# MRBR_2020-10-03_09-19-58.net
KiCad netlist of a schematic drawn in EasyEDA
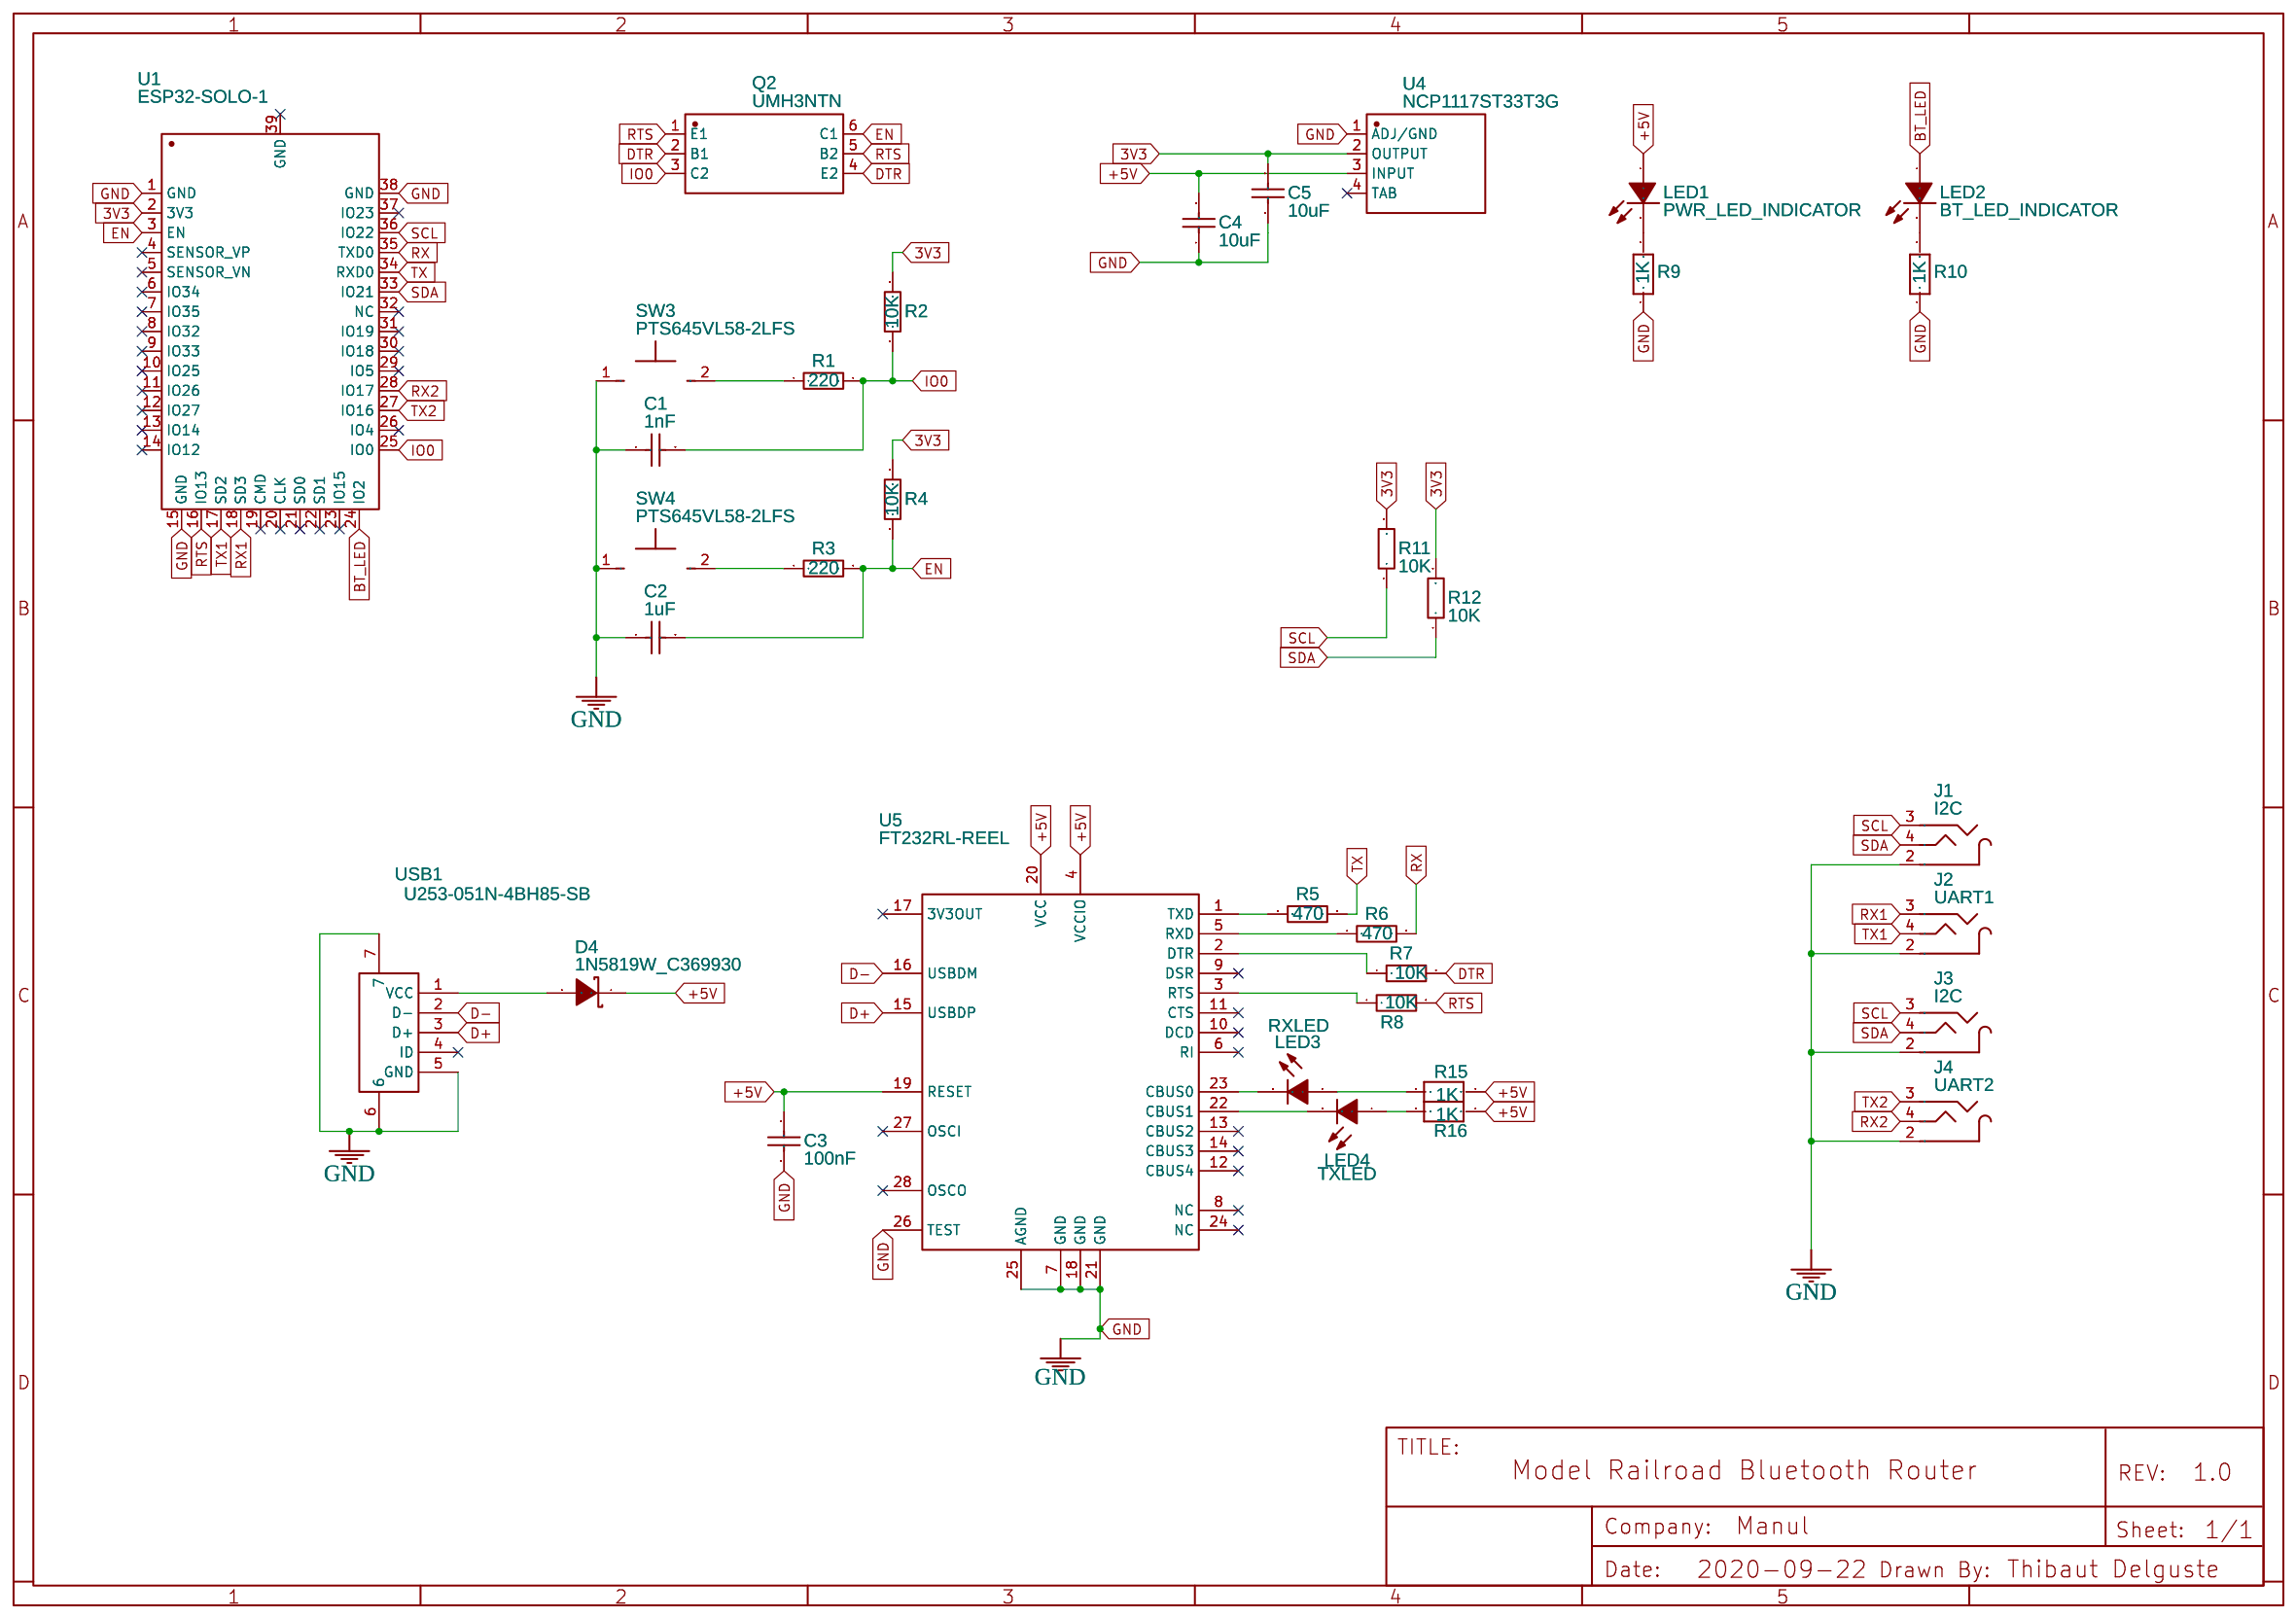
[diagram p0: schematic sheet]

(export (version "E")
  (design (tool "Eeschema 10.0.6"))
  (components
    (comp (ref "C1")
      (value "1nF")
      (fields
        (field (name "BOM_Manufacturer Part") "1206B102K500NT")
        (field (name "BOM_Supplier Part") "C1845")
      )
      (libsource (lib "") (part "1206B102K500NT"))
    )
    (comp (ref "C2")
      (value "1uF")
      (fields
        (field (name "BOM_Manufacturer Part") "1206B102K500NT")
        (field (name "BOM_Supplier Part") "C1845")
      )
      (libsource (lib "") (part "1206B102K500NT"))
    )
    (comp (ref "C3")
      (value "100nF")
      (fields
        (field (name "BOM_Manufacturer Part") "CL31B104KBCNNNC")
        (field (name "BOM_Supplier Part") "C24497")
      )
      (libsource (lib "") (part "CL31B104KBCNNNC"))
    )
    (comp (ref "C4")
      (value "10uF")
      (fields
        (field (name "BOM_Manufacturer Part") "CL31A106KAHNNNE")
        (field (name "BOM_Supplier Part") "C9807")
      )
      (libsource (lib "") (part "CL31A106KAHNNNE"))
    )
    (comp (ref "C5")
      (value "10uF")
      (fields
        (field (name "BOM_Manufacturer Part") "CL31A106KAHNNNE")
        (field (name "BOM_Supplier Part") "C9807")
      )
      (libsource (lib "") (part "CL31A106KAHNNNE"))
    )
    (comp (ref "D4")
      (value "1N5819W_C369930")
      (fields (field (name "BOM_Manufacturer Part") "1N5819W") (field (name "BOM_Supplier Part") "C369930"))
      (libsource (lib "") (part "1N5819W_C369930"))
    )
    (comp (ref "J1")
      (value "I2C")
      (fields (field (name "BOM_Manufacturer Part") "PJ313D") (field (name "BOM_Supplier Part") "C18167"))
      (libsource (lib "") (part "PJ313D"))
    )
    (comp (ref "J2")
      (value "UART1")
      (fields (field (name "BOM_Manufacturer Part") "PJ313D") (field (name "BOM_Supplier Part") "C18167"))
      (libsource (lib "") (part "PJ313D"))
    )
    (comp (ref "J3")
      (value "I2C")
      (fields (field (name "BOM_Manufacturer Part") "PJ313D") (field (name "BOM_Supplier Part") "C18167"))
      (libsource (lib "") (part "PJ313D"))
    )
    (comp (ref "J4")
      (value "UART2")
      (fields (field (name "BOM_Manufacturer Part") "PJ313D") (field (name "BOM_Supplier Part") "C18167"))
      (libsource (lib "") (part "PJ313D"))
    )
    (comp (ref "LED1")
      (value "PWR_LED_INDICATOR")
      (fields
        (field (name "BOM_Manufacturer Part") "FC-3215HRK-620D")
        (field (name "BOM_Supplier Part") "C84270")
      )
      (libsource (lib "") (part "FC-3215HRK-620D"))
    )
    (comp (ref "LED2")
      (value "BT_LED_INDICATOR")
      (fields
        (field (name "BOM_Manufacturer Part") "FC-3215HRK-620D")
        (field (name "BOM_Supplier Part") "C84270")
      )
      (libsource (lib "") (part "FC-3215HRK-620D"))
    )
    (comp (ref "LED3")
      (value "RXLED")
      (fields
        (field (name "BOM_Manufacturer Part") "15-21SYGC/S530-E2/TR8")
        (field (name "BOM_Supplier Part") "C73550")
      )
      (libsource (lib "") (part "15-21SYGC/S530-E2/TR8_1"))
    )
    (comp (ref "LED4")
      (value "TXLED")
      (fields
        (field (name "BOM_Manufacturer Part") "15-21SYGC/S530-E2/TR8")
        (field (name "BOM_Supplier Part") "C73550")
      )
      (libsource (lib "") (part "15-21SYGC/S530-E2/TR8"))
    )
    (comp (ref "Q2")
      (value "UMH3NTN")
      (fields (field (name "BOM_Supplier Part") "C123008"))
      (libsource (lib "") (part "UMH3NTN"))
    )
    (comp (ref "R1")
      (value "220")
      (fields
        (field (name "BOM_Manufacturer Part") "CR1206F42200G")
        (field (name "BOM_Supplier Part") "C102128")
      )
      (libsource (lib "") (part "CR1206F42200G"))
    )
    (comp (ref "R2")
      (value "10K")
      (fields
        (field (name "BOM_Manufacturer Part") "1206W4F1002T5E")
        (field (name "BOM_Supplier Part") "C17902")
      )
      (libsource (lib "") (part "1206W4F1002T5E"))
    )
    (comp (ref "R3")
      (value "220")
      (fields
        (field (name "BOM_Manufacturer Part") "CR1206F42200G")
        (field (name "BOM_Supplier Part") "C102128")
      )
      (libsource (lib "") (part "CR1206F42200G"))
    )
    (comp (ref "R4")
      (value "10K")
      (fields
        (field (name "BOM_Manufacturer Part") "1206W4F1002T5E")
        (field (name "BOM_Supplier Part") "C17902")
      )
      (libsource (lib "") (part "1206W4F1002T5E"))
    )
    (comp (ref "R5")
      (value "470")
      (fields
        (field (name "BOM_Manufacturer Part") "RCT06470RFLF")
        (field (name "BOM_Supplier Part") "C185720")
      )
      (libsource (lib "") (part "RCT06470RFLF"))
    )
    (comp (ref "R6")
      (value "470")
      (fields
        (field (name "BOM_Manufacturer Part") "RCT06470RFLF")
        (field (name "BOM_Supplier Part") "C185720")
      )
      (libsource (lib "") (part "RCT06470RFLF"))
    )
    (comp (ref "R7")
      (value "10K")
      (fields
        (field (name "BOM_Manufacturer Part") "1206W4J0102T5E")
        (field (name "BOM_Supplier Part") "C1469")
      )
      (libsource (lib "") (part "1206W4J0102T5E"))
    )
    (comp (ref "R8")
      (value "10K")
      (fields
        (field (name "BOM_Manufacturer Part") "1206W4J0102T5E")
        (field (name "BOM_Supplier Part") "C1469")
      )
      (libsource (lib "") (part "1206W4J0102T5E"))
    )
    (comp (ref "R9") (value "1K") (libsource (lib "") (part "Unknown_825_-675")))
    (comp (ref "R10") (value "1K") (libsource (lib "") (part "Unknown_965_-675")))
    (comp (ref "R11")
      (value "10K")
      (fields
        (field (name "BOM_Manufacturer Part") "1206W4J0102T5E")
        (field (name "BOM_Supplier Part") "C1469")
      )
      (libsource (lib "") (part "1206W4J0102T5E_1"))
    )
    (comp (ref "R12")
      (value "10K")
      (fields
        (field (name "BOM_Manufacturer Part") "1206W4J0102T5E")
        (field (name "BOM_Supplier Part") "C1469")
      )
      (libsource (lib "") (part "1206W4J0102T5E_1"))
    )
    (comp (ref "R15") (value "1K") (libsource (lib "") (part "Unknown_725_-260")))
    (comp (ref "R16") (value "1K") (libsource (lib "") (part "Unknown_725_-250")))
    (comp (ref "SW3")
      (value "PTS645VL58-2LFS")
      (fields (field (name "BOM_Supplier Part") "C221892"))
      (libsource (lib "") (part "Unknown_325_-630"))
    )
    (comp (ref "SW4")
      (value "PTS645VL58-2LFS")
      (fields (field (name "BOM_Supplier Part") "C221892"))
      (libsource (lib "") (part "Unknown_325_-535"))
    )
    (comp (ref "U1")
      (value "ESP32-SOLO-1")
      (fields (field (name "BOM_Supplier Part") "C473005"))
      (libsource (lib "") (part "ESP32-SOLO-1"))
    )
    (comp (ref "U4")
      (value "NCP1117ST33T3G")
      (fields (field (name "BOM_Supplier Part") "C26537"))
      (libsource (lib "") (part "NCP1117ST33T3G"))
    )
    (comp (ref "U5")
      (value "FT232RL-REEL")
      (fields (field (name "BOM_Supplier Part") "C8690"))
      (libsource (lib "") (part "Unknown_530_-270"))
    )
    (comp (ref "USB1")
      (value "U253-051N-4BH85-SB")
      (fields (field (name "BOM_Supplier Part") "C319177"))
      (libsource (lib "") (part "U253-051N-4BH85-SB"))
    )
  )
  (nets
    (net (code "1") (name "+5V") (class "Default")
      (node (ref "C3") (pin "2") (pinfunction "2_2") (pintype "input"))
      (node (ref "C4") (pin "2") (pinfunction "2_2") (pintype "input"))
      (node (ref "D4") (pin "1") (pinfunction "K_1") (pintype "unspecified"))
      (node (ref "LED1") (pin "1") (pinfunction "A_1") (pintype "unspecified"))
      (node (ref "R15") (pin "2") (pinfunction "2_2") (pintype "bidirectional"))
      (node (ref "R16") (pin "2") (pinfunction "2_2") (pintype "bidirectional"))
      (node (ref "U4") (pin "3") (pinfunction "INPUT_3") (pintype "unspecified"))
      (node (ref "U5") (pin "19") (pinfunction "RESET_19") (pintype "unspecified"))
      (node (ref "U5") (pin "20") (pinfunction "VCC_20") (pintype "passive"))
      (node (ref "U5") (pin "4") (pinfunction "VCCIO_4") (pintype "passive"))
    )
    (net (code "2") (name "3V3") (class "Default")
      (node (ref "C5") (pin "2") (pinfunction "2_2") (pintype "input"))
      (node (ref "R11") (pin "2") (pinfunction "2_2") (pintype "input"))
      (node (ref "R12") (pin "2") (pinfunction "2_2") (pintype "input"))
      (node (ref "R2") (pin "2") (pinfunction "2_2") (pintype "input"))
      (node (ref "R4") (pin "2") (pinfunction "2_2") (pintype "input"))
      (node (ref "U1") (pin "2") (pinfunction "3V3_2") (pintype "unspecified"))
      (node (ref "U4") (pin "2") (pinfunction "OUTPUT_2") (pintype "unspecified"))
    )
    (net (code "3") (name "BT_LED") (class "Default")
      (node (ref "LED2") (pin "1") (pinfunction "A_1") (pintype "unspecified"))
      (node (ref "U1") (pin "24") (pinfunction "IO2_24") (pintype "unspecified"))
    )
    (net (code "4") (name "D+") (class "Default")
      (node (ref "U5") (pin "15") (pinfunction "USBDP_15") (pintype "bidirectional"))
      (node (ref "USB1") (pin "3") (pinfunction "D+_3") (pintype "unspecified"))
    )
    (net (code "5") (name "D-") (class "Default")
      (node (ref "U5") (pin "16") (pinfunction "USBDM_16") (pintype "bidirectional"))
      (node (ref "USB1") (pin "2") (pinfunction "D-_2") (pintype "unspecified"))
    )
    (net (code "6") (name "DTR") (class "Default")
      (node (ref "Q2") (pin "2") (pinfunction "B1_2") (pintype "unspecified"))
      (node (ref "Q2") (pin "4") (pinfunction "E2_4") (pintype "unspecified"))
      (node (ref "R7") (pin "2") (pinfunction "2_2") (pintype "input"))
    )
    (net (code "7") (name "EN") (class "Default")
      (node (ref "C2") (pin "2") (pinfunction "2_2") (pintype "input"))
      (node (ref "Q2") (pin "6") (pinfunction "C1_6") (pintype "unspecified"))
      (node (ref "R3") (pin "2") (pinfunction "2_2") (pintype "input"))
      (node (ref "R4") (pin "1") (pinfunction "1_1") (pintype "input"))
      (node (ref "U1") (pin "3") (pinfunction "EN_3") (pintype "unspecified"))
    )
    (net (code "8") (name "GND") (class "Default")
      (node (ref "C1") (pin "1") (pinfunction "1_1") (pintype "input"))
      (node (ref "C2") (pin "1") (pinfunction "1_1") (pintype "input"))
      (node (ref "C3") (pin "1") (pinfunction "1_1") (pintype "input"))
      (node (ref "C4") (pin "1") (pinfunction "1_1") (pintype "input"))
      (node (ref "C5") (pin "1") (pinfunction "1_1") (pintype "input"))
      (node (ref "J1") (pin "2") (pinfunction "2_2") (pintype "input"))
      (node (ref "J2") (pin "2") (pinfunction "2_2") (pintype "input"))
      (node (ref "J3") (pin "2") (pinfunction "2_2") (pintype "input"))
      (node (ref "J4") (pin "2") (pinfunction "2_2") (pintype "input"))
      (node (ref "R10") (pin "1") (pinfunction "1_1") (pintype "bidirectional"))
      (node (ref "R9") (pin "1") (pinfunction "1_1") (pintype "bidirectional"))
      (node (ref "SW3") (pin "1") (pinfunction "1_1") (pintype "input"))
      (node (ref "SW4") (pin "1") (pinfunction "1_1") (pintype "input"))
      (node (ref "U1") (pin "1") (pinfunction "GND_1") (pintype "unspecified"))
      (node (ref "U1") (pin "15") (pinfunction "GND_15") (pintype "unspecified"))
      (node (ref "U1") (pin "38") (pinfunction "GND_38") (pintype "unspecified"))
      (node (ref "U4") (pin "1") (pinfunction "ADJ/GND_1") (pintype "unspecified"))
      (node (ref "U5") (pin "18") (pinfunction "GND_18") (pintype "passive"))
      (node (ref "U5") (pin "21") (pinfunction "GND_21") (pintype "passive"))
      (node (ref "U5") (pin "25") (pinfunction "AGND_25") (pintype "passive"))
      (node (ref "U5") (pin "26") (pinfunction "TEST_26") (pintype "unspecified"))
      (node (ref "U5") (pin "7") (pinfunction "GND_7") (pintype "passive"))
      (node (ref "USB1") (pin "5") (pinfunction "GND_5") (pintype "unspecified"))
      (node (ref "USB1") (pin "6") (pinfunction "6_6") (pintype "unspecified"))
      (node (ref "USB1") (pin "7") (pinfunction "7_7") (pintype "unspecified"))
    )
    (net (code "9") (name "IO0") (class "Default")
      (node (ref "C1") (pin "2") (pinfunction "2_2") (pintype "input"))
      (node (ref "Q2") (pin "3") (pinfunction "C2_3") (pintype "unspecified"))
      (node (ref "R1") (pin "2") (pinfunction "2_2") (pintype "input"))
      (node (ref "R2") (pin "1") (pinfunction "1_1") (pintype "input"))
      (node (ref "U1") (pin "25") (pinfunction "IO0_25") (pintype "unspecified"))
    )
    (net (code "10") (name "Net-(D4-A)") (class "Default")
      (node (ref "D4") (pin "2") (pinfunction "A_2") (pintype "unspecified"))
      (node (ref "USB1") (pin "1") (pinfunction "VCC_1") (pintype "unspecified"))
    )
    (net (code "11") (name "Net-(LED1-K)") (class "Default")
      (node (ref "LED1") (pin "2") (pinfunction "K_2") (pintype "unspecified"))
      (node (ref "R9") (pin "2") (pinfunction "2_2") (pintype "bidirectional"))
    )
    (net (code "12") (name "Net-(LED2-K)") (class "Default")
      (node (ref "LED2") (pin "2") (pinfunction "K_2") (pintype "unspecified"))
      (node (ref "R10") (pin "2") (pinfunction "2_2") (pintype "bidirectional"))
    )
    (net (code "13") (name "Net-(LED3-A)") (class "Default")
      (node (ref "LED3") (pin "1") (pinfunction "A_1") (pintype "input"))
      (node (ref "R15") (pin "1") (pinfunction "1_1") (pintype "bidirectional"))
    )
    (net (code "14") (name "Net-(LED3-C)") (class "Default")
      (node (ref "LED3") (pin "2") (pinfunction "C_2") (pintype "input"))
      (node (ref "U5") (pin "23") (pinfunction "CBUS0_23") (pintype "bidirectional"))
    )
    (net (code "15") (name "Net-(LED4-A)") (class "Default")
      (node (ref "LED4") (pin "1") (pinfunction "A_1") (pintype "input"))
      (node (ref "R16") (pin "1") (pinfunction "1_1") (pintype "bidirectional"))
    )
    (net (code "16") (name "Net-(LED4-C)") (class "Default")
      (node (ref "LED4") (pin "2") (pinfunction "C_2") (pintype "input"))
      (node (ref "U5") (pin "22") (pinfunction "CBUS1_22") (pintype "bidirectional"))
    )
    (net (code "17") (name "Net-(R1-Pad1)") (class "Default")
      (node (ref "R1") (pin "1") (pinfunction "1_1") (pintype "input"))
      (node (ref "SW3") (pin "2") (pinfunction "2_2") (pintype "input"))
    )
    (net (code "18") (name "Net-(R3-Pad1)") (class "Default")
      (node (ref "R3") (pin "1") (pinfunction "1_1") (pintype "input"))
      (node (ref "SW4") (pin "2") (pinfunction "2_2") (pintype "input"))
    )
    (net (code "19") (name "Net-(U5-DTR)") (class "Default")
      (node (ref "R7") (pin "1") (pinfunction "1_1") (pintype "input"))
      (node (ref "U5") (pin "2") (pinfunction "DTR_2") (pintype "output"))
    )
    (net (code "20") (name "Net-(U5-RTS)") (class "Default")
      (node (ref "R8") (pin "1") (pinfunction "1_1") (pintype "input"))
      (node (ref "U5") (pin "3") (pinfunction "RTS_3") (pintype "output"))
    )
    (net (code "21") (name "Net-(U5-RXD)") (class "Default")
      (node (ref "R6") (pin "1") (pinfunction "1_1") (pintype "unspecified"))
      (node (ref "U5") (pin "5") (pinfunction "RXD_5") (pintype "unspecified"))
    )
    (net (code "22") (name "Net-(U5-TXD)") (class "Default")
      (node (ref "R5") (pin "1") (pinfunction "1_1") (pintype "unspecified"))
      (node (ref "U5") (pin "1") (pinfunction "TXD_1") (pintype "output"))
    )
    (net (code "23") (name "RTS") (class "Default")
      (node (ref "Q2") (pin "1") (pinfunction "E1_1") (pintype "unspecified"))
      (node (ref "Q2") (pin "5") (pinfunction "B2_5") (pintype "unspecified"))
      (node (ref "R8") (pin "2") (pinfunction "2_2") (pintype "input"))
      (node (ref "U1") (pin "16") (pinfunction "IO13_16") (pintype "unspecified"))
    )
    (net (code "24") (name "RX") (class "Default")
      (node (ref "R6") (pin "2") (pinfunction "2_2") (pintype "unspecified"))
      (node (ref "U1") (pin "35") (pinfunction "TXD0_35") (pintype "unspecified"))
    )
    (net (code "25") (name "RX1") (class "Default")
      (node (ref "J2") (pin "3") (pinfunction "3_3") (pintype "input"))
      (node (ref "U1") (pin "18") (pinfunction "SD3_18") (pintype "unspecified"))
    )
    (net (code "26") (name "RX2") (class "Default")
      (node (ref "J4") (pin "4") (pinfunction "4_4") (pintype "input"))
      (node (ref "U1") (pin "28") (pinfunction "IO17_28") (pintype "unspecified"))
    )
    (net (code "27") (name "SCL") (class "Default")
      (node (ref "J1") (pin "3") (pinfunction "3_3") (pintype "input"))
      (node (ref "J3") (pin "3") (pinfunction "3_3") (pintype "input"))
      (node (ref "R11") (pin "1") (pinfunction "1_1") (pintype "input"))
      (node (ref "U1") (pin "36") (pinfunction "IO22_36") (pintype "unspecified"))
    )
    (net (code "28") (name "SDA") (class "Default")
      (node (ref "J1") (pin "4") (pinfunction "4_4") (pintype "input"))
      (node (ref "J3") (pin "4") (pinfunction "4_4") (pintype "input"))
      (node (ref "R12") (pin "1") (pinfunction "1_1") (pintype "input"))
      (node (ref "U1") (pin "33") (pinfunction "IO21_33") (pintype "unspecified"))
    )
    (net (code "29") (name "TX") (class "Default")
      (node (ref "R5") (pin "2") (pinfunction "2_2") (pintype "unspecified"))
      (node (ref "U1") (pin "34") (pinfunction "RXD0_34") (pintype "unspecified"))
    )
    (net (code "30") (name "TX1") (class "Default")
      (node (ref "J2") (pin "4") (pinfunction "4_4") (pintype "input"))
      (node (ref "U1") (pin "17") (pinfunction "SD2_17") (pintype "unspecified"))
    )
    (net (code "31") (name "TX2") (class "Default")
      (node (ref "J4") (pin "3") (pinfunction "3_3") (pintype "input"))
      (node (ref "U1") (pin "27") (pinfunction "IO16_27") (pintype "unspecified"))
    )
    (net (code "32") (name "unconnected-(U1-CLK-Pad20)") (class "Default")
      (node (ref "U1") (pin "20") (pinfunction "CLK_20") (pintype "unspecified+no_connect"))
    )
    (net (code "33") (name "unconnected-(U1-CMD-Pad19)") (class "Default")
      (node (ref "U1") (pin "19") (pinfunction "CMD_19") (pintype "unspecified+no_connect"))
    )
    (net (code "34") (name "unconnected-(U1-GND-Pad39)") (class "Default")
      (node (ref "U1") (pin "39") (pinfunction "GND_39") (pintype "unspecified+no_connect"))
    )
    (net (code "35") (name "unconnected-(U1-IO4-Pad26)") (class "Default")
      (node (ref "U1") (pin "26") (pinfunction "IO4_26") (pintype "unspecified+no_connect"))
    )
    (net (code "36") (name "unconnected-(U1-IO5-Pad29)") (class "Default")
      (node (ref "U1") (pin "29") (pinfunction "IO5_29") (pintype "unspecified+no_connect"))
    )
    (net (code "37") (name "unconnected-(U1-IO12-Pad14)") (class "Default")
      (node (ref "U1") (pin "14") (pinfunction "IO12_14") (pintype "unspecified+no_connect"))
    )
    (net (code "38") (name "unconnected-(U1-IO14-Pad13)") (class "Default")
      (node (ref "U1") (pin "13") (pinfunction "IO14_13") (pintype "unspecified+no_connect"))
    )
    (net (code "39") (name "unconnected-(U1-IO15-Pad23)") (class "Default")
      (node (ref "U1") (pin "23") (pinfunction "IO15_23") (pintype "unspecified+no_connect"))
    )
    (net (code "40") (name "unconnected-(U1-IO18-Pad30)") (class "Default")
      (node (ref "U1") (pin "30") (pinfunction "IO18_30") (pintype "unspecified+no_connect"))
    )
    (net (code "41") (name "unconnected-(U1-IO19-Pad31)") (class "Default")
      (node (ref "U1") (pin "31") (pinfunction "IO19_31") (pintype "unspecified+no_connect"))
    )
    (net (code "42") (name "unconnected-(U1-IO23-Pad37)") (class "Default")
      (node (ref "U1") (pin "37") (pinfunction "IO23_37") (pintype "unspecified+no_connect"))
    )
    (net (code "43") (name "unconnected-(U1-IO25-Pad10)") (class "Default")
      (node (ref "U1") (pin "10") (pinfunction "IO25_10") (pintype "unspecified+no_connect"))
    )
    (net (code "44") (name "unconnected-(U1-IO26-Pad11)") (class "Default")
      (node (ref "U1") (pin "11") (pinfunction "IO26_11") (pintype "unspecified+no_connect"))
    )
    (net (code "45") (name "unconnected-(U1-IO27-Pad12)") (class "Default")
      (node (ref "U1") (pin "12") (pinfunction "IO27_12") (pintype "unspecified+no_connect"))
    )
    (net (code "46") (name "unconnected-(U1-IO32-Pad8)") (class "Default")
      (node (ref "U1") (pin "8") (pinfunction "IO32_8") (pintype "unspecified+no_connect"))
    )
    (net (code "47") (name "unconnected-(U1-IO33-Pad9)") (class "Default")
      (node (ref "U1") (pin "9") (pinfunction "IO33_9") (pintype "unspecified+no_connect"))
    )
    (net (code "48") (name "unconnected-(U1-IO34-Pad6)") (class "Default")
      (node (ref "U1") (pin "6") (pinfunction "IO34_6") (pintype "unspecified+no_connect"))
    )
    (net (code "49") (name "unconnected-(U1-IO35-Pad7)") (class "Default")
      (node (ref "U1") (pin "7") (pinfunction "IO35_7") (pintype "unspecified+no_connect"))
    )
    (net (code "50") (name "unconnected-(U1-NC-Pad32)") (class "Default")
      (node (ref "U1") (pin "32") (pinfunction "NC_32") (pintype "unspecified+no_connect"))
    )
    (net (code "51") (name "unconnected-(U1-SD0-Pad21)") (class "Default")
      (node (ref "U1") (pin "21") (pinfunction "SD0_21") (pintype "unspecified+no_connect"))
    )
    (net (code "52") (name "unconnected-(U1-SD1-Pad22)") (class "Default")
      (node (ref "U1") (pin "22") (pinfunction "SD1_22") (pintype "unspecified+no_connect"))
    )
    (net (code "53") (name "unconnected-(U1-SENSOR_VN-Pad5)") (class "Default")
      (node (ref "U1") (pin "5") (pinfunction "SENSOR_VN_5") (pintype "unspecified+no_connect"))
    )
    (net (code "54") (name "unconnected-(U1-SENSOR_VP-Pad4)") (class "Default")
      (node (ref "U1") (pin "4") (pinfunction "SENSOR_VP_4") (pintype "unspecified+no_connect"))
    )
    (net (code "55") (name "unconnected-(U4-TAB-Pad4)") (class "Default")
      (node (ref "U4") (pin "4") (pinfunction "TAB_4") (pintype "unspecified+no_connect"))
    )
    (net (code "56") (name "unconnected-(U5-3V3OUT-Pad17)") (class "Default")
      (node (ref "U5") (pin "17") (pinfunction "3V3OUT_17") (pintype "output+no_connect"))
    )
    (net (code "57") (name "unconnected-(U5-CBUS2-Pad13)") (class "Default")
      (node (ref "U5") (pin "13") (pinfunction "CBUS2_13") (pintype "bidirectional+no_connect"))
    )
    (net (code "58") (name "unconnected-(U5-CBUS3-Pad14)") (class "Default")
      (node (ref "U5") (pin "14") (pinfunction "CBUS3_14") (pintype "bidirectional+no_connect"))
    )
    (net (code "59") (name "unconnected-(U5-CBUS4-Pad12)") (class "Default")
      (node (ref "U5") (pin "12") (pinfunction "CBUS4_12") (pintype "bidirectional+no_connect"))
    )
    (net (code "60") (name "unconnected-(U5-CTS-Pad11)") (class "Default")
      (node (ref "U5") (pin "11") (pinfunction "CTS_11") (pintype "unspecified+no_connect"))
    )
    (net (code "61") (name "unconnected-(U5-DCD-Pad10)") (class "Default")
      (node (ref "U5") (pin "10") (pinfunction "DCD_10") (pintype "unspecified+no_connect"))
    )
    (net (code "62") (name "unconnected-(U5-DSR-Pad9)") (class "Default")
      (node (ref "U5") (pin "9") (pinfunction "DSR_9") (pintype "unspecified+no_connect"))
    )
    (net (code "63") (name "unconnected-(U5-NC-Pad8)") (class "Default")
      (node (ref "U5") (pin "8") (pinfunction "NC_8") (pintype "unspecified+no_connect"))
    )
    (net (code "64") (name "unconnected-(U5-NC-Pad24)") (class "Default")
      (node (ref "U5") (pin "24") (pinfunction "NC_24") (pintype "unspecified+no_connect"))
    )
    (net (code "65") (name "unconnected-(U5-OSCI-Pad27)") (class "Default")
      (node (ref "U5") (pin "27") (pinfunction "OSCI_27") (pintype "unspecified+no_connect"))
    )
    (net (code "66") (name "unconnected-(U5-OSCO-Pad28)") (class "Default")
      (node (ref "U5") (pin "28") (pinfunction "OSCO_28") (pintype "output+no_connect"))
    )
    (net (code "67") (name "unconnected-(U5-RI-Pad6)") (class "Default")
      (node (ref "U5") (pin "6") (pinfunction "RI_6") (pintype "unspecified+no_connect"))
    )
    (net (code "68") (name "unconnected-(USB1-ID-Pad4)") (class "Default")
      (node (ref "USB1") (pin "4") (pinfunction "ID_4") (pintype "unspecified+no_connect"))
    )
  )
)
